# IO_master_nano2.net
KiCad netlist of a schematic drawn in EAGLE
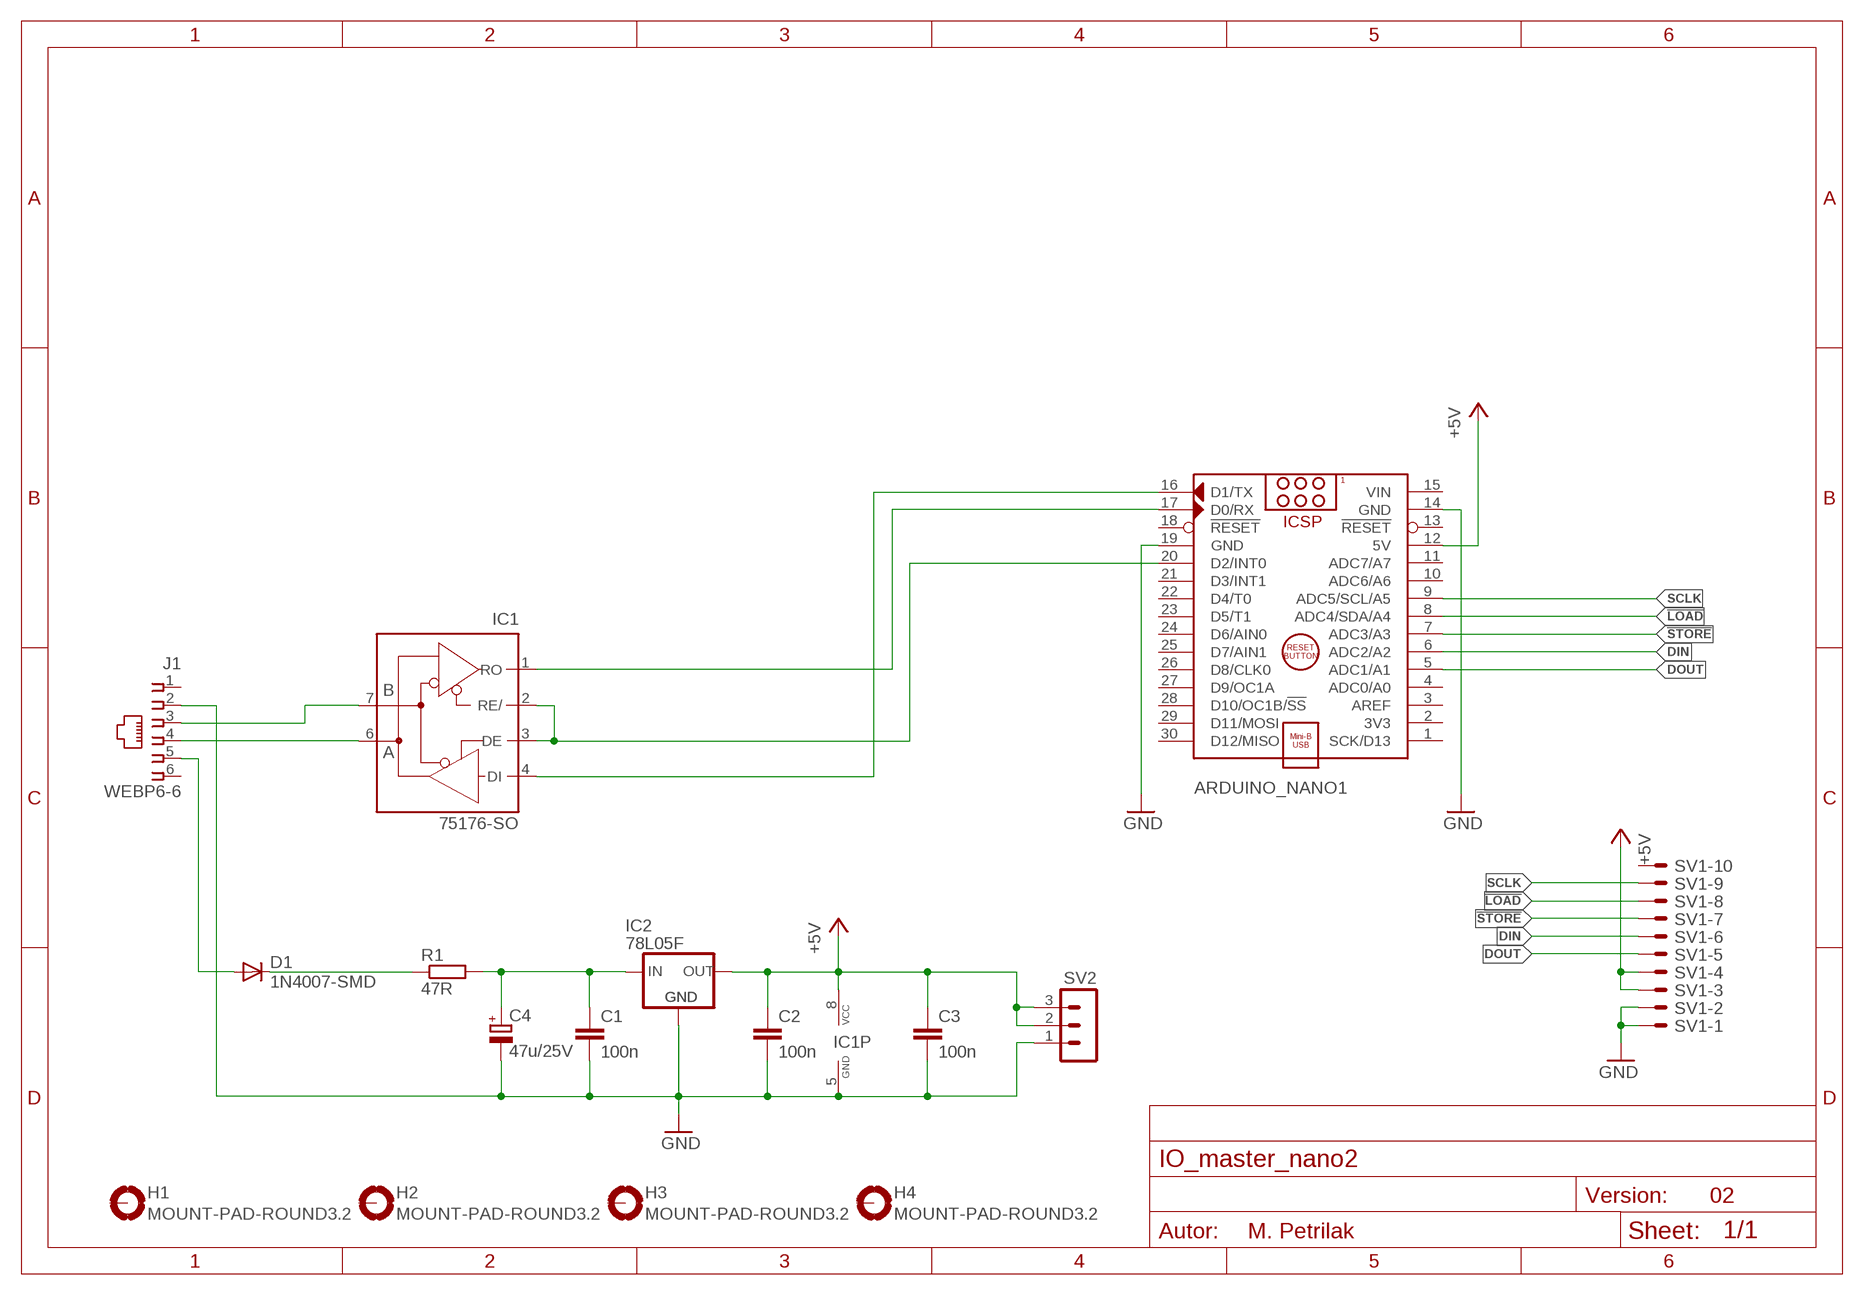
[diagram p0: schematic, sheet 1]

(export (version "E")
  (design (tool "Eeschema 10.0.6"))
  (components
    (comp (ref "ARDUINO_NANO1")
      (value "ARDUINO_NANO_2")
      (footprint "eagle-import:ARDUINO_NANO2")
      (libsource (lib "eagle-import") (part "ARDUINO_NANO_2"))
    )
    (comp (ref "C1")
      (value "100n")
      (footprint "eagle-import:C1206")
      (libsource (lib "eagle-import") (part "C-EUC1206"))
    )
    (comp (ref "C2")
      (value "100n")
      (footprint "eagle-import:C1206")
      (libsource (lib "eagle-import") (part "C-EUC1206"))
    )
    (comp (ref "C3")
      (value "100n")
      (footprint "eagle-import:C1206")
      (libsource (lib "eagle-import") (part "C-EUC1206"))
    )
    (comp (ref "C4")
      (value "47u/25V")
      (footprint "eagle-import:E2,5-7")
      (libsource (lib "eagle-import") (part "CPOL-EUE2.5-7"))
    )
    (comp (ref "D1")
      (value "1N4007-SMD")
      (footprint "eagle-import:SMA-DO214AC")
      (libsource (lib "eagle-import") (part "1N400-SMD7"))
    )
    (comp (ref "H1")
      (value "MOUNT-PAD-ROUND3.2")
      (footprint "eagle-import:3,2-PAD")
      (libsource (lib "eagle-import") (part "MOUNT-PAD-ROUND3.2"))
    )
    (comp (ref "H2")
      (value "MOUNT-PAD-ROUND3.2")
      (footprint "eagle-import:3,2-PAD")
      (libsource (lib "eagle-import") (part "MOUNT-PAD-ROUND3.2"))
    )
    (comp (ref "H3")
      (value "MOUNT-PAD-ROUND3.2")
      (footprint "eagle-import:3,2-PAD")
      (libsource (lib "eagle-import") (part "MOUNT-PAD-ROUND3.2"))
    )
    (comp (ref "H4")
      (value "MOUNT-PAD-ROUND3.2")
      (footprint "eagle-import:3,2-PAD")
      (libsource (lib "eagle-import") (part "MOUNT-PAD-ROUND3.2"))
    )
    (comp (ref "IC1")
      (value "75176-SO")
      (footprint "eagle-import:SO08")
      (libsource (lib "eagle-import") (part "75176-SO"))
    )
    (comp (ref "IC2")
      (value "78L05F")
      (footprint "eagle-import:SOT89")
      (libsource (lib "eagle-import") (part "78LF05"))
    )
    (comp (ref "J1")
      (value "WEBP6-6")
      (footprint "eagle-import:WEBP6-6_SPEC2")
      (libsource (lib "eagle-import") (part "WEBP6-6_SPEC2"))
    )
    (comp (ref "R1")
      (value "47R")
      (footprint "eagle-import:0204_5")
      (libsource (lib "eagle-import") (part "R-EU_0204/5"))
    )
    (comp (ref "SV1")
      (value "ML10E")
      (footprint "eagle-import:ML10")
      (libsource (lib "eagle-import") (part "ML10?E"))
    )
    (comp (ref "SV2")
      (value "MA03-1_NO")
      (footprint "eagle-import:MA03-1_NO")
      (libsource (lib "eagle-import") (part "MA03-1_NO"))
    )
  )
  (nets
    (net (code "1") (name "+5V") (class "Default")
      (node (ref "ARDUINO_NANO1") (pin "12") (pinfunction "5V_12") (pintype "power_in"))
      (node (ref "C2") (pin "1") (pinfunction "1_1") (pintype "passive"))
      (node (ref "C3") (pin "1") (pinfunction "1_1") (pintype "passive"))
      (node (ref "IC1") (pin "8") (pinfunction "VCC_8") (pintype "power_in"))
      (node (ref "IC2") (pin "1") (pinfunction "VO_1") (pintype "passive"))
      (node (ref "SV1") (pin "3") (pinfunction "S_3") (pintype "passive"))
      (node (ref "SV1") (pin "4") (pinfunction "S_4") (pintype "passive"))
      (node (ref "SV2") (pin "2") (pinfunction "2_2") (pintype "passive"))
      (node (ref "SV2") (pin "3") (pinfunction "3_3") (pintype "passive"))
    )
    (net (code "2") (name "/VIN") (class "Default")
      (node (ref "ARDUINO_NANO1") (pin "15") (pinfunction "VIN_15") (pintype "power_in"))
    )
    (net (code "3") (name "/~{LOAD}") (class "Default")
      (node (ref "ARDUINO_NANO1") (pin "8") (pinfunction "ADC4/SDA/A4_8") (pintype "bidirectional"))
      (node (ref "SV1") (pin "8") (pinfunction "S_8") (pintype "passive"))
    )
    (net (code "4") (name "/~{STORE}") (class "Default")
      (node (ref "ARDUINO_NANO1") (pin "7") (pinfunction "ADC3/A3_7") (pintype "bidirectional"))
      (node (ref "SV1") (pin "7") (pinfunction "S_7") (pintype "passive"))
    )
    (net (code "5") (name "DIN") (class "Default")
      (node (ref "ARDUINO_NANO1") (pin "6") (pinfunction "ADC2/A2_6") (pintype "bidirectional"))
      (node (ref "SV1") (pin "6") (pinfunction "S_6") (pintype "passive"))
    )
    (net (code "6") (name "DOUT") (class "Default")
      (node (ref "ARDUINO_NANO1") (pin "5") (pinfunction "ADC1/A1_5") (pintype "bidirectional"))
      (node (ref "SV1") (pin "5") (pinfunction "S_5") (pintype "passive"))
    )
    (net (code "7") (name "GND") (class "Default")
      (node (ref "ARDUINO_NANO1") (pin "14") (pinfunction "GND_14") (pintype "power_in"))
      (node (ref "ARDUINO_NANO1") (pin "19") (pinfunction "GND_19") (pintype "power_in"))
      (node (ref "C1") (pin "2") (pinfunction "2_2") (pintype "passive"))
      (node (ref "C2") (pin "2") (pinfunction "2_2") (pintype "passive"))
      (node (ref "C3") (pin "2") (pinfunction "2_2") (pintype "passive"))
      (node (ref "C4") (pin "-") (pinfunction "-_-") (pintype "passive"))
      (node (ref "IC1") (pin "5") (pinfunction "GND_5") (pintype "power_in"))
      (node (ref "IC2") (pin "2") (pinfunction "GND_2") (pintype "passive"))
      (node (ref "IC2") (pin "2@1") (pinfunction "GND_2@1") (pintype "passive"))
      (node (ref "J1") (pin "2") (pinfunction "2_2") (pintype "passive"))
      (node (ref "SV1") (pin "1") (pinfunction "S_1") (pintype "passive"))
      (node (ref "SV1") (pin "2") (pinfunction "S_2") (pintype "passive"))
      (node (ref "SV2") (pin "1") (pinfunction "1_1") (pintype "passive"))
    )
    (net (code "8") (name "Net-(ARDUINO_NANO1-D0{slash}RX)") (class "Default")
      (node (ref "ARDUINO_NANO1") (pin "17") (pinfunction "D0/RX_17") (pintype "bidirectional"))
      (node (ref "IC1") (pin "1") (pinfunction "RO_1") (pintype "output"))
    )
    (net (code "9") (name "Net-(ARDUINO_NANO1-D1{slash}TX)") (class "Default")
      (node (ref "ARDUINO_NANO1") (pin "16") (pinfunction "D1/TX_16") (pintype "bidirectional"))
      (node (ref "IC1") (pin "4") (pinfunction "DI_4") (pintype "input"))
    )
    (net (code "10") (name "Net-(ARDUINO_NANO1-D2{slash}INT0)") (class "Default")
      (node (ref "ARDUINO_NANO1") (pin "20") (pinfunction "D2/INT0_20") (pintype "bidirectional"))
      (node (ref "IC1") (pin "2") (pinfunction "RE/_2") (pintype "input"))
      (node (ref "IC1") (pin "3") (pinfunction "DE_3") (pintype "input"))
    )
    (net (code "11") (name "Net-(D1-C)") (class "Default")
      (node (ref "D1") (pin "K") (pinfunction "C_K") (pintype "passive"))
      (node (ref "R1") (pin "1") (pinfunction "1_1") (pintype "passive"))
    )
    (net (code "12") (name "Net-(D1-PadA)") (class "Default")
      (node (ref "D1") (pin "A") (pinfunction "A_A") (pintype "passive"))
      (node (ref "J1") (pin "5") (pinfunction "5_5") (pintype "passive"))
    )
    (net (code "13") (name "Net-(IC1A-A)") (class "Default")
      (node (ref "IC1") (pin "6") (pinfunction "A_6") (pintype "passive"))
      (node (ref "J1") (pin "4") (pinfunction "4_4") (pintype "passive"))
    )
    (net (code "14") (name "Net-(IC1A-B)") (class "Default")
      (node (ref "IC1") (pin "7") (pinfunction "B_7") (pintype "passive"))
      (node (ref "J1") (pin "3") (pinfunction "3_3") (pintype "passive"))
    )
    (net (code "15") (name "Net-(IC2-VI)") (class "Default")
      (node (ref "C1") (pin "1") (pinfunction "1_1") (pintype "passive"))
      (node (ref "C4") (pin "+") (pinfunction "+_+") (pintype "passive"))
      (node (ref "IC2") (pin "3") (pinfunction "VI_3") (pintype "input"))
      (node (ref "R1") (pin "2") (pinfunction "2_2") (pintype "passive"))
    )
    (net (code "16") (name "SCLK") (class "Default")
      (node (ref "ARDUINO_NANO1") (pin "9") (pinfunction "ADC5/SCL/A5_9") (pintype "bidirectional"))
      (node (ref "SV1") (pin "9") (pinfunction "S_9") (pintype "passive"))
    )
    (net (code "17") (name "unconnected-(ARDUINO_NANO1-3V3-Pad2)") (class "Default")
      (node (ref "ARDUINO_NANO1") (pin "2") (pinfunction "3V3_2") (pintype "output"))
    )
    (net (code "18") (name "unconnected-(ARDUINO_NANO1-ADC0{slash}A0-Pad4)") (class "Default")
      (node (ref "ARDUINO_NANO1") (pin "4") (pinfunction "ADC0/A0_4") (pintype "bidirectional"))
    )
    (net (code "19") (name "unconnected-(ARDUINO_NANO1-ADC6{slash}A6-Pad10)") (class "Default")
      (node (ref "ARDUINO_NANO1") (pin "10") (pinfunction "ADC6/A6_10") (pintype "bidirectional"))
    )
    (net (code "20") (name "unconnected-(ARDUINO_NANO1-ADC7{slash}A7-Pad11)") (class "Default")
      (node (ref "ARDUINO_NANO1") (pin "11") (pinfunction "ADC7/A7_11") (pintype "bidirectional"))
    )
    (net (code "21") (name "unconnected-(ARDUINO_NANO1-AREF-Pad3)") (class "Default")
      (node (ref "ARDUINO_NANO1") (pin "3") (pinfunction "AREF_3") (pintype "input"))
    )
    (net (code "22") (name "unconnected-(ARDUINO_NANO1-D3{slash}INT1-Pad21)") (class "Default")
      (node (ref "ARDUINO_NANO1") (pin "21") (pinfunction "D3/INT1_21") (pintype "bidirectional"))
    )
    (net (code "23") (name "unconnected-(ARDUINO_NANO1-D4{slash}T0-Pad22)") (class "Default")
      (node (ref "ARDUINO_NANO1") (pin "22") (pinfunction "D4/T0_22") (pintype "bidirectional"))
    )
    (net (code "24") (name "unconnected-(ARDUINO_NANO1-D5{slash}T1-Pad23)") (class "Default")
      (node (ref "ARDUINO_NANO1") (pin "23") (pinfunction "D5/T1_23") (pintype "bidirectional"))
    )
    (net (code "25") (name "unconnected-(ARDUINO_NANO1-D6{slash}AIN0-Pad24)") (class "Default")
      (node (ref "ARDUINO_NANO1") (pin "24") (pinfunction "D6/AIN0_24") (pintype "bidirectional"))
    )
    (net (code "26") (name "unconnected-(ARDUINO_NANO1-D7{slash}AIN1-Pad25)") (class "Default")
      (node (ref "ARDUINO_NANO1") (pin "25") (pinfunction "D7/AIN1_25") (pintype "bidirectional"))
    )
    (net (code "27") (name "unconnected-(ARDUINO_NANO1-D8{slash}CLK0-Pad26)") (class "Default")
      (node (ref "ARDUINO_NANO1") (pin "26") (pinfunction "D8/CLK0_26") (pintype "bidirectional"))
    )
    (net (code "28") (name "unconnected-(ARDUINO_NANO1-D9{slash}OC1A-Pad27)") (class "Default")
      (node (ref "ARDUINO_NANO1") (pin "27") (pinfunction "D9/OC1A_27") (pintype "bidirectional"))
    )
    (net (code "29") (name "unconnected-(ARDUINO_NANO1-D10{slash}OC1B{slash}~{SS}-Pad28)") (class "Default")
      (node (ref "ARDUINO_NANO1") (pin "28") (pinfunction "D10/OC1B/~{SS}_28") (pintype "bidirectional"))
    )
    (net (code "30") (name "unconnected-(ARDUINO_NANO1-D11{slash}MOSI-Pad29)") (class "Default")
      (node (ref "ARDUINO_NANO1") (pin "29") (pinfunction "D11/MOSI_29") (pintype "bidirectional"))
    )
    (net (code "31") (name "unconnected-(ARDUINO_NANO1-D12{slash}MISO-Pad30)") (class "Default")
      (node (ref "ARDUINO_NANO1") (pin "30") (pinfunction "D12/MISO_30") (pintype "bidirectional"))
    )
    (net (code "32") (name "unconnected-(ARDUINO_NANO1-SCK{slash}D13-Pad1)") (class "Default")
      (node (ref "ARDUINO_NANO1") (pin "1") (pinfunction "SCK/D13_1") (pintype "bidirectional"))
    )
    (net (code "33") (name "unconnected-(ARDUINO_NANO1-~{RESET}-Pad13)") (class "Default")
      (node (ref "ARDUINO_NANO1") (pin "13") (pinfunction "~{RESET}_13") (pintype "input"))
    )
    (net (code "34") (name "unconnected-(ARDUINO_NANO1-~{RESET}-Pad18)") (class "Default")
      (node (ref "ARDUINO_NANO1") (pin "18") (pinfunction "~{RESET}_18") (pintype "input"))
    )
    (net (code "35") (name "unconnected-(H1-MOUNT-PadB3,2)") (class "Default")
      (node (ref "H1") (pin "B3,2") (pinfunction "MOUNT_B3,2") (pintype "passive"))
    )
    (net (code "36") (name "unconnected-(H2-MOUNT-PadB3,2)") (class "Default")
      (node (ref "H2") (pin "B3,2") (pinfunction "MOUNT_B3,2") (pintype "passive"))
    )
    (net (code "37") (name "unconnected-(H3-MOUNT-PadB3,2)") (class "Default")
      (node (ref "H3") (pin "B3,2") (pinfunction "MOUNT_B3,2") (pintype "passive"))
    )
    (net (code "38") (name "unconnected-(H4-MOUNT-PadB3,2)") (class "Default")
      (node (ref "H4") (pin "B3,2") (pinfunction "MOUNT_B3,2") (pintype "passive"))
    )
    (net (code "39") (name "unconnected-(J1-Pad1)") (class "Default")
      (node (ref "J1") (pin "1") (pinfunction "1_1") (pintype "passive"))
    )
    (net (code "40") (name "unconnected-(J1-Pad6)") (class "Default")
      (node (ref "J1") (pin "6") (pinfunction "6_6") (pintype "passive"))
    )
    (net (code "41") (name "unconnected-(SV1B-S-Pad10)") (class "Default")
      (node (ref "SV1") (pin "10") (pinfunction "S_10") (pintype "passive"))
    )
  )
)
